# MSB-PCB-1R2.net
KiCad netlist of a schematic drawn in Altium Designer
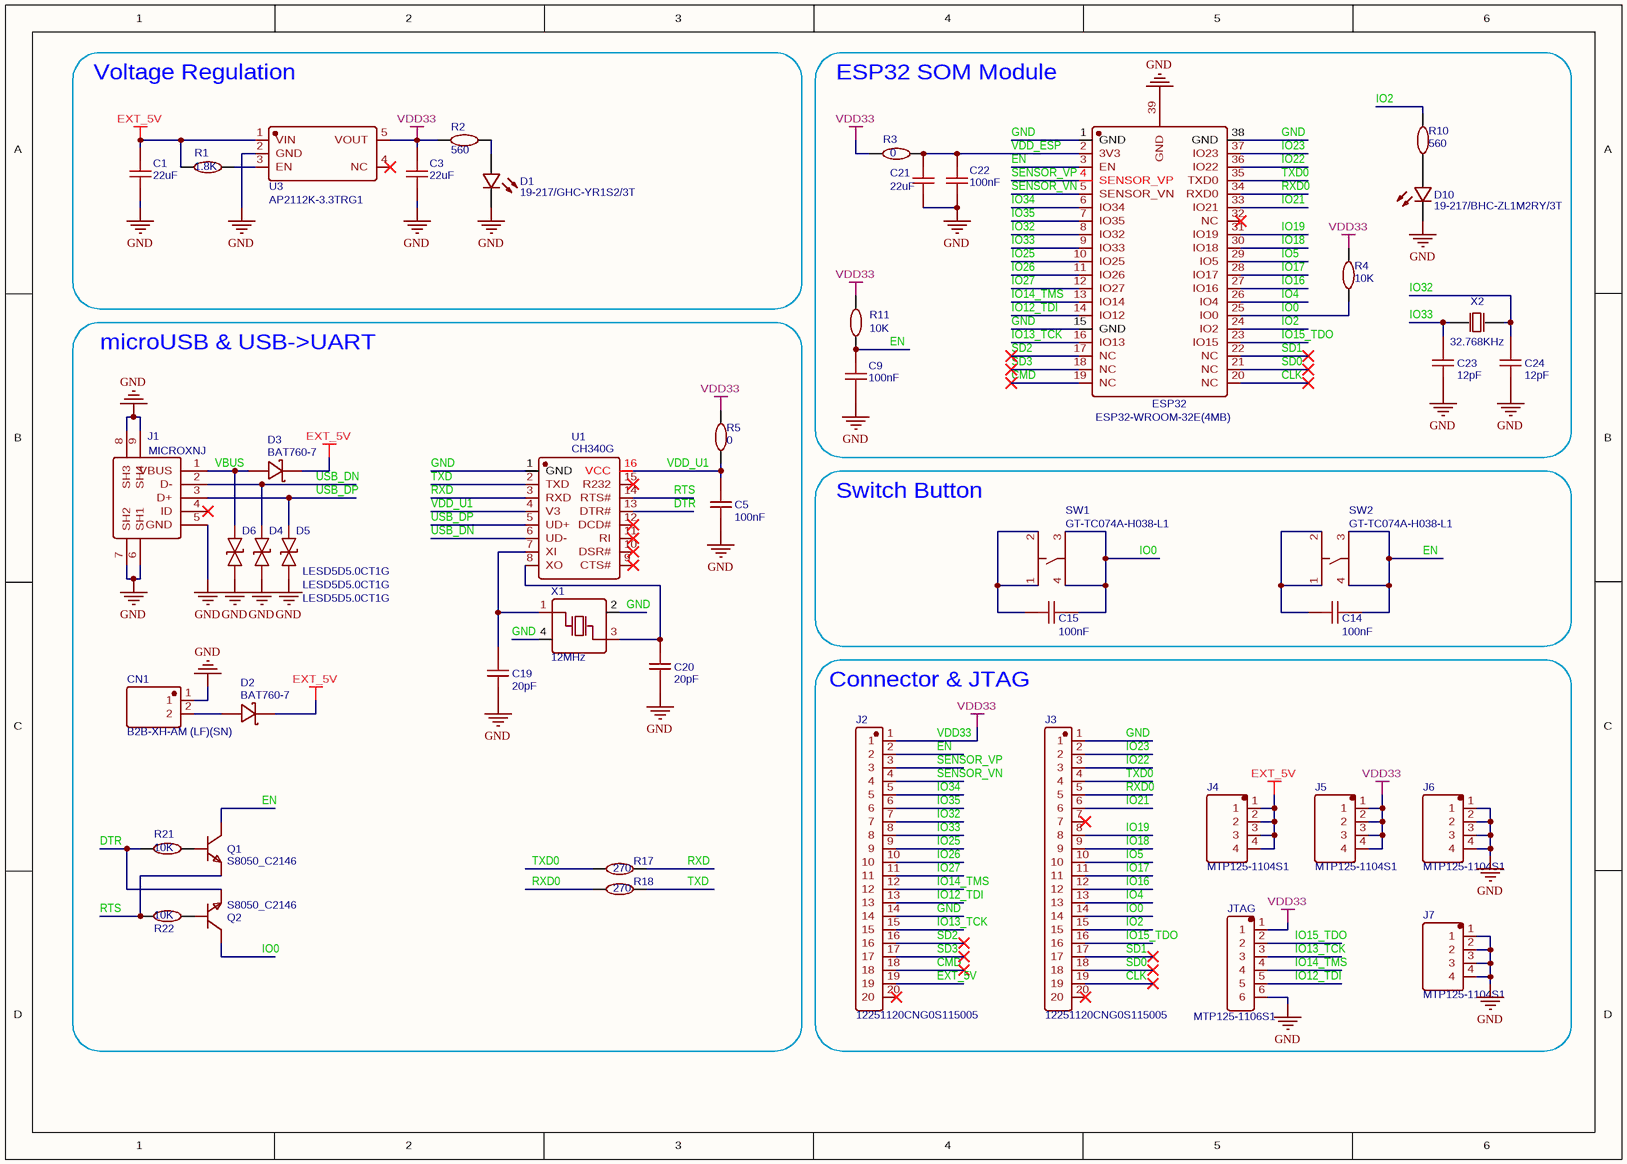
[diagram p0: MSB-PCB-1R2.schdoc]

(export (version "E")
  (design (tool "Eeschema 10.0.6"))
  (components
    (comp (ref "C1")
      (value "22uF")
      (footprint "C0603")
      (fields
        (field (name "BOM_SUPPLIER PART") "C167429")
        (field (name "BOM_MANUFACTURER PART") "GRM188R61A226ME15L")
        (field (name "CONTRIBUTOR") "LCSC")
      )
      (libsource (lib "altium-import") (part "root_1_22uF_"))
    )
    (comp (ref "C3")
      (value "22uF")
      (footprint "C0603")
      (fields
        (field (name "BOM_SUPPLIER PART") "C167429")
        (field (name "BOM_MANUFACTURER PART") "GRM188R61A226ME15L")
        (field (name "CONTRIBUTOR") "LCSC")
      )
      (libsource (lib "altium-import") (part "root_1_22uF_"))
    )
    (comp (ref "C5")
      (value "100nF")
      (footprint "C0603")
      (fields
        (field (name "BOM_MANUFACTURER PART") "CC0603KRX7R9BB104")
        (field (name "BOM_SUPPLIER PART") "C14663")
      )
      (libsource (lib "altium-import") (part "root_3_100nF_"))
    )
    (comp (ref "C9")
      (value "100nF")
      (footprint "C0603")
      (fields
        (field (name "BOM_MANUFACTURER PART") "CC0603KRX7R9BB104")
        (field (name "BOM_SUPPLIER PART") "C14663")
      )
      (libsource (lib "altium-import") (part "root_1_100nF_"))
    )
    (comp (ref "C14")
      (value "100nF")
      (footprint "C0603")
      (fields
        (field (name "BOM_MANUFACTURER PART") "CC0603KRX7R9BB104")
        (field (name "BOM_SUPPLIER PART") "C14663")
      )
      (libsource (lib "altium-import") (part "root_0_100nF_"))
    )
    (comp (ref "C15")
      (value "100nF")
      (footprint "C0603")
      (fields
        (field (name "BOM_MANUFACTURER PART") "CC0603KRX7R9BB104")
        (field (name "BOM_SUPPLIER PART") "C14663")
      )
      (libsource (lib "altium-import") (part "root_0_100nF_"))
    )
    (comp (ref "C19")
      (value "20pF")
      (footprint "C0603")
      (fields
        (field (name "BOM_SUPPLIER PART") "C376774")
        (field (name "BOM_MANUFACTURER PART") "TCC0603COG200J500CT")
        (field (name "CONTRIBUTOR") "LCSC")
      )
      (libsource (lib "altium-import") (part "root_0_20pF_"))
    )
    (comp (ref "C20")
      (value "20pF")
      (footprint "C0603")
      (fields
        (field (name "BOM_SUPPLIER PART") "C376774")
        (field (name "BOM_MANUFACTURER PART") "TCC0603COG200J500CT")
        (field (name "CONTRIBUTOR") "LCSC")
      )
      (libsource (lib "altium-import") (part "root_0_20pF_"))
    )
    (comp (ref "C21")
      (value "22uF")
      (footprint "C0603")
      (fields
        (field (name "BOM_SUPPLIER PART") "C167429")
        (field (name "BOM_MANUFACTURER PART") "GRM188R61A226ME15L")
        (field (name "CONTRIBUTOR") "LCSC")
      )
      (libsource (lib "altium-import") (part "root_1_22uF_"))
    )
    (comp (ref "C22")
      (value "100nF")
      (footprint "C0603")
      (fields
        (field (name "BOM_MANUFACTURER PART") "CC0603KRX7R9BB104")
        (field (name "BOM_SUPPLIER PART") "C14663")
      )
      (libsource (lib "altium-import") (part "root_1_100nF_"))
    )
    (comp (ref "C23")
      (value "12pF")
      (footprint "C0603")
      (fields
        (field (name "BOM_SUPPLIER PART") "C376767")
        (field (name "BOM_MANUFACTURER PART") "TCC0603COG120J500CT")
        (field (name "CONTRIBUTOR") "LCSC")
      )
      (libsource (lib "altium-import") (part "root_0_12pF_"))
    )
    (comp (ref "C24")
      (value "12pF")
      (footprint "C0603")
      (fields
        (field (name "BOM_SUPPLIER PART") "C376767")
        (field (name "BOM_MANUFACTURER PART") "TCC0603COG120J500CT")
        (field (name "CONTRIBUTOR") "LCSC")
      )
      (libsource (lib "altium-import") (part "root_0_12pF_"))
    )
    (comp (ref "CN1")
      (value "B2B-XH-AM (LF)(SN)")
      (footprint "CONN-TH_B2B-XH-AM-LF-SN")
      (fields (field (name "BOM_SUPPLIER PART") "C161869") (field (name "CONTRIBUTOR") "LCSC"))
      (libsource (lib "altium-import") (part "root_0_mirrored_B2B-XH-AM (LF)(SN)_"))
    )
    (comp (ref "D1")
      (value "19-217/GHC-YR1S2/3T")
      (footprint "LED0603-R-RD")
      (fields (field (name "BOM_SUPPLIER PART") "C72043"))
      (libsource (lib "altium-import") (part "root_3_19-217/GHC-YR1S2/3T_"))
    )
    (comp (ref "D2")
      (value "BAT760-7")
      (footprint "SOD-323_L1.8-W1.3-LS2.5-RD")
      (fields (field (name "BOM_SUPPLIER PART") "C124187") (field (name "CONTRIBUTOR") "LCSC"))
      (libsource (lib "altium-import") (part "root_2_BAT760-7_"))
    )
    (comp (ref "D3")
      (value "BAT760-7")
      (footprint "SOD-323_L1.8-W1.3-LS2.5-RD")
      (fields (field (name "BOM_SUPPLIER PART") "C124187") (field (name "CONTRIBUTOR") "LCSC"))
      (libsource (lib "altium-import") (part "root_2_BAT760-7_"))
    )
    (comp (ref "D4")
      (value "LESD5D5.0CT1G")
      (footprint "SOD-523_L1.2-W0.8-LS1.6-BI")
      (fields (field (name "BOM_SUPPLIER PART") "C383211") (field (name "CONTRIBUTOR") "LCSC"))
      (libsource (lib "altium-import") (part "root_1_LESD5D5.0CT1G_"))
    )
    (comp (ref "D5")
      (value "LESD5D5.0CT1G")
      (footprint "SOD-523_L1.2-W0.8-LS1.6-BI")
      (fields (field (name "BOM_SUPPLIER PART") "C383211") (field (name "CONTRIBUTOR") "LCSC"))
      (libsource (lib "altium-import") (part "root_1_LESD5D5.0CT1G_"))
    )
    (comp (ref "D6")
      (value "LESD5D5.0CT1G")
      (footprint "SOD-523_L1.2-W0.8-LS1.6-BI")
      (fields (field (name "BOM_SUPPLIER PART") "C383211") (field (name "CONTRIBUTOR") "LCSC"))
      (libsource (lib "altium-import") (part "root_1_LESD5D5.0CT1G_"))
    )
    (comp (ref "D10")
      (value "19-217/BHC-ZL1M2RY/3T")
      (footprint "LED0603-R-RD")
      (fields (field (name "BOM_SUPPLIER PART") "C72041"))
      (libsource (lib "altium-import") (part "root_1_19-217/BHC-ZL1M2RY/3T_"))
    )
    (comp (ref "ESP32")
      (value "ESP32-WROOM-32E(4MB)")
      (footprint "WIFI-SMD_ESP32-WROOM-32E")
      (fields (field (name "BOM_SUPPLIER PART") "C701341") (field (name "CONTRIBUTOR") "LCSC"))
      (libsource (lib "altium-import") (part "root_0_ESP32-WROOM-32E(4MB)_"))
    )
    (comp (ref "J1")
      (value "MICROXNJ")
      (footprint "MICRO-USB-SMD_MICROXNJ")
      (fields
        (field (name "BOM_SUPPLIER PART") "C404969")
        (field (name "BOM_MANUFACTURER PART") "MicroXNJ")
        (field (name "CONTRIBUTOR") "LCSC")
      )
      (libsource (lib "altium-import") (part "root_2_MICROXNJ_"))
    )
    (comp (ref "J2")
      (value "12251120CNG0S115005")
      (footprint "HDR-TH_19P-P2.54-V")
      (fields (field (name "BOM_SUPPLIER PART") "C429964") (field (name "CONTRIBUTOR") "LCSC"))
      (libsource (lib "altium-import") (part "root_0_mirrored_12251120CNG0S115005_"))
    )
    (comp (ref "J3")
      (value "12251120CNG0S115005")
      (footprint "HDR-TH_19P-P2.54-V")
      (fields (field (name "BOM_SUPPLIER PART") "C429964") (field (name "CONTRIBUTOR") "LCSC"))
      (libsource (lib "altium-import") (part "root_0_mirrored_12251120CNG0S115005_"))
    )
    (comp (ref "J4")
      (value "MTP125-1104S1")
      (footprint "HDR-TH_4P-P2.54-V")
      (fields (field (name "BOM_SUPPLIER PART") "C358686") (field (name "CONTRIBUTOR") "LCSC"))
      (libsource (lib "altium-import") (part "root_0_mirrored_MTP125-1104S1_"))
    )
    (comp (ref "J5")
      (value "MTP125-1104S1")
      (footprint "HDR-TH_4P-P2.54-V")
      (fields (field (name "BOM_SUPPLIER PART") "C358686") (field (name "CONTRIBUTOR") "LCSC"))
      (libsource (lib "altium-import") (part "root_0_mirrored_MTP125-1104S1_"))
    )
    (comp (ref "J6")
      (value "MTP125-1104S1")
      (footprint "HDR-TH_4P-P2.54-V")
      (fields (field (name "BOM_SUPPLIER PART") "C358686") (field (name "CONTRIBUTOR") "LCSC"))
      (libsource (lib "altium-import") (part "root_0_mirrored_MTP125-1104S1_"))
    )
    (comp (ref "J7")
      (value "MTP125-1104S1")
      (footprint "HDR-TH_4P-P2.54-V")
      (fields (field (name "BOM_SUPPLIER PART") "C358686") (field (name "CONTRIBUTOR") "LCSC"))
      (libsource (lib "altium-import") (part "root_0_mirrored_MTP125-1104S1_"))
    )
    (comp (ref "JTAG")
      (value "MTP125-1106S1")
      (footprint "HDR-TH_6P-P2.54-V")
      (fields (field (name "BOM_SUPPLIER PART") "C358688") (field (name "CONTRIBUTOR") "LCSC"))
      (libsource (lib "altium-import") (part "root_0_mirrored_MTP125-1106S1_"))
    )
    (comp (ref "Q1")
      (value "S8050_C2146")
      (footprint "SOT-23-3_L3.0-W1.7-P0.95-LS2.9-BR")
      (fields (field (name "BOM_MANUFACTURER PART") "S8050") (field (name "BOM_SUPPLIER PART") "C2146"))
      (libsource (lib "") (part "root_0_S8050_C2146__1"))
    )
    (comp (ref "Q2")
      (value "S8050_C2146")
      (footprint "SOT-23-3_L3.0-W1.7-P0.95-LS2.9-BR")
      (fields (field (name "BOM_MANUFACTURER PART") "S8050") (field (name "BOM_SUPPLIER PART") "C2146"))
      (libsource (lib "altium-import") (part "root_0_S8050_C2146_"))
    )
    (comp (ref "R1")
      (value "1.8K")
      (footprint "R0603")
      (fields
        (field (name "BOM_MANUFACTURER PART") "0603WAJ0182T5E")
        (field (name "BOM_SUPPLIER PART") "C25991")
      )
      (libsource (lib "altium-import") (part "root_0_1.8K_"))
    )
    (comp (ref "R2")
      (value "560")
      (footprint "R0603")
      (fields
        (field (name "BOM_MANUFACTURER PART") "0603WAF5600T5E")
        (field (name "BOM_SUPPLIER PART") "C23204")
      )
      (libsource (lib "altium-import") (part "root_2_560_"))
    )
    (comp (ref "R3")
      (value "0")
      (footprint "R0603")
      (fields
        (field (name "BOM_MANUFACTURER PART") "0603WAF0000T5E")
        (field (name "BOM_SUPPLIER PART") "C21189")
      )
      (libsource (lib "altium-import") (part "root_0_0_"))
    )
    (comp (ref "R4")
      (value "10K")
      (footprint "R0603")
      (fields
        (field (name "BOM_MANUFACTURER PART") "0603WAJ0103T5E")
        (field (name "BOM_SUPPLIER PART") "C15401")
      )
      (libsource (lib "altium-import") (part "root_1_10K_"))
    )
    (comp (ref "R5")
      (value "0")
      (footprint "R0603")
      (fields
        (field (name "BOM_MANUFACTURER PART") "0603WAF0000T5E")
        (field (name "BOM_SUPPLIER PART") "C21189")
      )
      (libsource (lib "altium-import") (part "root_1_0_"))
    )
    (comp (ref "R10")
      (value "560")
      (footprint "R0603")
      (fields
        (field (name "BOM_MANUFACTURER PART") "0603WAF5600T5E")
        (field (name "BOM_SUPPLIER PART") "C23204")
      )
      (libsource (lib "altium-import") (part "root_1_560_"))
    )
    (comp (ref "R11")
      (value "10K")
      (footprint "R0603")
      (fields
        (field (name "BOM_MANUFACTURER PART") "0603WAJ0103T5E")
        (field (name "BOM_SUPPLIER PART") "C15401")
      )
      (libsource (lib "altium-import") (part "root_1_10K_"))
    )
    (comp (ref "R17")
      (value "270")
      (footprint "R0603")
      (fields
        (field (name "BOM_MANUFACTURER PART") "0603WAJ0271T5E")
        (field (name "BOM_SUPPLIER PART") "C25223")
      )
      (libsource (lib "altium-import") (part "root_0_270_"))
    )
    (comp (ref "R18")
      (value "270")
      (footprint "R0603")
      (fields
        (field (name "BOM_MANUFACTURER PART") "0603WAJ0271T5E")
        (field (name "BOM_SUPPLIER PART") "C25223")
      )
      (libsource (lib "altium-import") (part "root_0_270_"))
    )
    (comp (ref "R21")
      (value "10K")
      (footprint "R0603")
      (fields
        (field (name "BOM_MANUFACTURER PART") "0603WAJ0103T5E")
        (field (name "BOM_SUPPLIER PART") "C15401")
      )
      (libsource (lib "altium-import") (part "root_0_10K_"))
    )
    (comp (ref "R22")
      (value "10K")
      (footprint "R0603")
      (fields
        (field (name "BOM_MANUFACTURER PART") "0603WAJ0103T5E")
        (field (name "BOM_SUPPLIER PART") "C15401")
      )
      (libsource (lib "altium-import") (part "root_0_10K_"))
    )
    (comp (ref "SW1")
      (value "GT-TC074A-H038-L1")
      (footprint "SW-SMD_4P-L4.5-W4.5-P3.00-LS7.0")
      (fields (field (name "BOM_SUPPLIER PART") "C843603") (field (name "CONTRIBUTOR") "LCSC"))
      (libsource (lib "altium-import") (part "root_1_GT-TC074A-H038-L1_"))
    )
    (comp (ref "SW2")
      (value "GT-TC074A-H038-L1")
      (footprint "SW-SMD_4P-L4.5-W4.5-P3.00-LS7.0")
      (fields (field (name "BOM_SUPPLIER PART") "C843603") (field (name "CONTRIBUTOR") "LCSC"))
      (libsource (lib "altium-import") (part "root_1_GT-TC074A-H038-L1_"))
    )
    (comp (ref "U1")
      (value "CH340G")
      (footprint "SOIC-16_L9.9-W3.9-P1.27-LS6.0-TL")
      (fields (field (name "BOM_SUPPLIER PART") "C14267"))
      (libsource (lib "altium-import") (part "root_0_CH340G_"))
    )
    (comp (ref "U3")
      (value "AP2112K-3.3TRG1")
      (footprint "SOT-25-5_L3.0-W1.8-P0.95-LS3.0-BR")
      (fields (field (name "BOM_SUPPLIER PART") "C51118") (field (name "CONTRIBUTOR") "LCSC"))
      (libsource (lib "altium-import") (part "root_0_AP2112K-3.3TRG1_"))
    )
    (comp (ref "X1")
      (value "12MHz")
      (footprint "OSC-SMD_4P-L3.2-W2.5-BL")
      (fields
        (field (name "BOM_MANUFACTURER PART") "X322512MSB4SI")
        (field (name "BOM_SUPPLIER PART") "C9002")
      )
      (libsource (lib "altium-import") (part "root_2_12MHz_"))
    )
    (comp (ref "X2")
      (value "32.768KHz")
      (footprint "OSC-SMD_L3.2-W1.5")
      (fields
        (field (name "BOM_SUPPLIER PART") "C271654")
        (field (name "BOM_MANUFACTURER PART") "SF32K32768D31T-12.5")
        (field (name "CONTRIBUTOR") "LCSC")
      )
      (libsource (lib "altium-import") (part "root_0_32.768KHz_"))
    )
  )
  (nets
    (net (code "1") (name "/CLK") (class "Default")
      (node (ref "ESP32") (pin "20") (pinfunction "NC_20") (pintype "passive"))
      (node (ref "J3") (pin "19") (pinfunction "19_19") (pintype "passive"))
    )
    (net (code "2") (name "/CMD") (class "Default")
      (node (ref "ESP32") (pin "19") (pinfunction "NC_19") (pintype "passive"))
      (node (ref "J2") (pin "18") (pinfunction "18_18") (pintype "passive"))
    )
    (net (code "3") (name "/DTR") (class "Default")
      (node (ref "Q2") (pin "2") (pinfunction "E_2") (pintype "passive"))
      (node (ref "R21") (pin "1") (pinfunction "1_1") (pintype "passive"))
      (node (ref "U1") (pin "13") (pinfunction "DTR#_13") (pintype "passive"))
    )
    (net (code "4") (name "/EN") (class "Default")
      (node (ref "C14") (pin "2") (pinfunction "2_2") (pintype "passive"))
      (node (ref "C9") (pin "2") (pinfunction "2_2") (pintype "passive"))
      (node (ref "ESP32") (pin "3") (pinfunction "EN_3") (pintype "passive"))
      (node (ref "J2") (pin "2") (pinfunction "2_2") (pintype "passive"))
      (node (ref "Q1") (pin "3") (pinfunction "C_3") (pintype "passive"))
      (node (ref "R11") (pin "1") (pinfunction "1_1") (pintype "passive"))
      (node (ref "SW2") (pin "3") (pinfunction "3_3") (pintype "passive"))
      (node (ref "SW2") (pin "4") (pinfunction "4_4") (pintype "passive"))
    )
    (net (code "5") (name "/IO0") (class "Default")
      (node (ref "C15") (pin "2") (pinfunction "2_2") (pintype "passive"))
      (node (ref "ESP32") (pin "25") (pinfunction "IO0_25") (pintype "passive"))
      (node (ref "J3") (pin "14") (pinfunction "14_14") (pintype "passive"))
      (node (ref "Q2") (pin "3") (pinfunction "C_3") (pintype "passive"))
      (node (ref "R4") (pin "1") (pinfunction "1_1") (pintype "passive"))
      (node (ref "SW1") (pin "3") (pinfunction "3_3") (pintype "passive"))
      (node (ref "SW1") (pin "4") (pinfunction "4_4") (pintype "passive"))
    )
    (net (code "6") (name "/IO2") (class "Default")
      (node (ref "ESP32") (pin "24") (pinfunction "IO2_24") (pintype "passive"))
      (node (ref "J3") (pin "15") (pinfunction "15_15") (pintype "passive"))
      (node (ref "R10") (pin "2") (pinfunction "2_2") (pintype "passive"))
    )
    (net (code "7") (name "/IO4") (class "Default")
      (node (ref "ESP32") (pin "26") (pinfunction "IO4_26") (pintype "passive"))
      (node (ref "J3") (pin "13") (pinfunction "13_13") (pintype "passive"))
    )
    (net (code "8") (name "/IO5") (class "Default")
      (node (ref "ESP32") (pin "29") (pinfunction "IO5_29") (pintype "passive"))
      (node (ref "J3") (pin "10") (pinfunction "10_10") (pintype "passive"))
    )
    (net (code "9") (name "/IO12_TDI") (class "Default")
      (node (ref "ESP32") (pin "14") (pinfunction "IO12_14") (pintype "passive"))
      (node (ref "J2") (pin "13") (pinfunction "13_13") (pintype "passive"))
      (node (ref "JTAG") (pin "5") (pinfunction "5_5") (pintype "passive"))
    )
    (net (code "10") (name "/IO13_TCK") (class "Default")
      (node (ref "ESP32") (pin "16") (pinfunction "IO13_16") (pintype "passive"))
      (node (ref "J2") (pin "15") (pinfunction "15_15") (pintype "passive"))
      (node (ref "JTAG") (pin "3") (pinfunction "3_3") (pintype "passive"))
    )
    (net (code "11") (name "/IO14_TMS") (class "Default")
      (node (ref "ESP32") (pin "13") (pinfunction "IO14_13") (pintype "passive"))
      (node (ref "J2") (pin "12") (pinfunction "12_12") (pintype "passive"))
      (node (ref "JTAG") (pin "4") (pinfunction "4_4") (pintype "passive"))
    )
    (net (code "12") (name "/IO15_TDO") (class "Default")
      (node (ref "ESP32") (pin "23") (pinfunction "IO15_23") (pintype "passive"))
      (node (ref "J3") (pin "16") (pinfunction "16_16") (pintype "passive"))
      (node (ref "JTAG") (pin "2") (pinfunction "2_2") (pintype "passive"))
    )
    (net (code "13") (name "/IO16") (class "Default")
      (node (ref "ESP32") (pin "27") (pinfunction "IO16_27") (pintype "passive"))
      (node (ref "J3") (pin "12") (pinfunction "12_12") (pintype "passive"))
    )
    (net (code "14") (name "/IO17") (class "Default")
      (node (ref "ESP32") (pin "28") (pinfunction "IO17_28") (pintype "passive"))
      (node (ref "J3") (pin "11") (pinfunction "11_11") (pintype "passive"))
    )
    (net (code "15") (name "/IO18") (class "Default")
      (node (ref "ESP32") (pin "30") (pinfunction "IO18_30") (pintype "passive"))
      (node (ref "J3") (pin "9") (pinfunction "9_9") (pintype "passive"))
    )
    (net (code "16") (name "/IO19") (class "Default")
      (node (ref "ESP32") (pin "31") (pinfunction "IO19_31") (pintype "passive"))
      (node (ref "J3") (pin "8") (pinfunction "8_8") (pintype "passive"))
    )
    (net (code "17") (name "/IO21") (class "Default")
      (node (ref "ESP32") (pin "33") (pinfunction "IO21_33") (pintype "passive"))
      (node (ref "J3") (pin "6") (pinfunction "6_6") (pintype "passive"))
    )
    (net (code "18") (name "/IO22") (class "Default")
      (node (ref "ESP32") (pin "36") (pinfunction "IO22_36") (pintype "passive"))
      (node (ref "J3") (pin "3") (pinfunction "3_3") (pintype "passive"))
    )
    (net (code "19") (name "/IO23") (class "Default")
      (node (ref "ESP32") (pin "37") (pinfunction "IO23_37") (pintype "passive"))
      (node (ref "J3") (pin "2") (pinfunction "2_2") (pintype "passive"))
    )
    (net (code "20") (name "/IO25") (class "Default")
      (node (ref "ESP32") (pin "10") (pinfunction "IO25_10") (pintype "passive"))
      (node (ref "J2") (pin "9") (pinfunction "9_9") (pintype "passive"))
    )
    (net (code "21") (name "/IO26") (class "Default")
      (node (ref "ESP32") (pin "11") (pinfunction "IO26_11") (pintype "passive"))
      (node (ref "J2") (pin "10") (pinfunction "10_10") (pintype "passive"))
    )
    (net (code "22") (name "/IO27") (class "Default")
      (node (ref "ESP32") (pin "12") (pinfunction "IO27_12") (pintype "passive"))
      (node (ref "J2") (pin "11") (pinfunction "11_11") (pintype "passive"))
    )
    (net (code "23") (name "/IO32") (class "Default")
      (node (ref "C24") (pin "2") (pinfunction "2_2") (pintype "passive"))
      (node (ref "ESP32") (pin "8") (pinfunction "IO32_8") (pintype "passive"))
      (node (ref "J2") (pin "7") (pinfunction "7_7") (pintype "passive"))
      (node (ref "X2") (pin "2") (pinfunction "OSC2_2") (pintype "passive"))
    )
    (net (code "24") (name "/IO33") (class "Default")
      (node (ref "C23") (pin "2") (pinfunction "2_2") (pintype "passive"))
      (node (ref "ESP32") (pin "9") (pinfunction "IO33_9") (pintype "passive"))
      (node (ref "J2") (pin "8") (pinfunction "8_8") (pintype "passive"))
      (node (ref "X2") (pin "1") (pinfunction "OSC1_1") (pintype "passive"))
    )
    (net (code "25") (name "/IO34") (class "Default")
      (node (ref "ESP32") (pin "6") (pinfunction "IO34_6") (pintype "passive"))
      (node (ref "J2") (pin "5") (pinfunction "5_5") (pintype "passive"))
    )
    (net (code "26") (name "/IO35") (class "Default")
      (node (ref "ESP32") (pin "7") (pinfunction "IO35_7") (pintype "passive"))
      (node (ref "J2") (pin "6") (pinfunction "6_6") (pintype "passive"))
    )
    (net (code "27") (name "/RTS") (class "Default")
      (node (ref "Q1") (pin "2") (pinfunction "E_2") (pintype "passive"))
      (node (ref "R22") (pin "1") (pinfunction "1_1") (pintype "passive"))
      (node (ref "U1") (pin "14") (pinfunction "RTS#_14") (pintype "passive"))
    )
    (net (code "28") (name "/RXD") (class "Default")
      (node (ref "R17") (pin "2") (pinfunction "2_2") (pintype "passive"))
      (node (ref "U1") (pin "3") (pinfunction "RXD_3") (pintype "passive"))
    )
    (net (code "29") (name "/RXD0") (class "Default")
      (node (ref "ESP32") (pin "34") (pinfunction "RXD0_34") (pintype "passive"))
      (node (ref "J3") (pin "5") (pinfunction "5_5") (pintype "passive"))
      (node (ref "R18") (pin "1") (pinfunction "1_1") (pintype "passive"))
    )
    (net (code "30") (name "/SD0") (class "Default")
      (node (ref "ESP32") (pin "21") (pinfunction "NC_21") (pintype "passive"))
      (node (ref "J3") (pin "18") (pinfunction "18_18") (pintype "passive"))
    )
    (net (code "31") (name "/SD1") (class "Default")
      (node (ref "ESP32") (pin "22") (pinfunction "NC_22") (pintype "passive"))
      (node (ref "J3") (pin "17") (pinfunction "17_17") (pintype "passive"))
    )
    (net (code "32") (name "/SD2") (class "Default")
      (node (ref "ESP32") (pin "17") (pinfunction "NC_17") (pintype "passive"))
      (node (ref "J2") (pin "16") (pinfunction "16_16") (pintype "passive"))
    )
    (net (code "33") (name "/SD3") (class "Default")
      (node (ref "ESP32") (pin "18") (pinfunction "NC_18") (pintype "passive"))
      (node (ref "J2") (pin "17") (pinfunction "17_17") (pintype "passive"))
    )
    (net (code "34") (name "/SENSOR_VN") (class "Default")
      (node (ref "ESP32") (pin "5") (pinfunction "SENSOR_VN_5") (pintype "passive"))
      (node (ref "J2") (pin "4") (pinfunction "4_4") (pintype "passive"))
    )
    (net (code "35") (name "/SENSOR_VP") (class "Default")
      (node (ref "ESP32") (pin "4") (pinfunction "SENSOR_VP_4") (pintype "passive"))
      (node (ref "J2") (pin "3") (pinfunction "3_3") (pintype "passive"))
    )
    (net (code "36") (name "/TXD") (class "Default")
      (node (ref "R18") (pin "2") (pinfunction "2_2") (pintype "passive"))
      (node (ref "U1") (pin "2") (pinfunction "TXD_2") (pintype "passive"))
    )
    (net (code "37") (name "/TXD0") (class "Default")
      (node (ref "ESP32") (pin "35") (pinfunction "TXD0_35") (pintype "passive"))
      (node (ref "J3") (pin "4") (pinfunction "4_4") (pintype "passive"))
      (node (ref "R17") (pin "1") (pinfunction "1_1") (pintype "passive"))
    )
    (net (code "38") (name "/USB_DN") (class "Default")
      (node (ref "D4") (pin "2") (pinfunction "2_2") (pintype "passive"))
      (node (ref "J1") (pin "2") (pinfunction "D-_2") (pintype "passive"))
      (node (ref "U1") (pin "6") (pinfunction "UD-_6") (pintype "passive"))
    )
    (net (code "39") (name "/USB_DP") (class "Default")
      (node (ref "D5") (pin "2") (pinfunction "2_2") (pintype "passive"))
      (node (ref "J1") (pin "3") (pinfunction "D+_3") (pintype "passive"))
      (node (ref "U1") (pin "5") (pinfunction "UD+_5") (pintype "passive"))
    )
    (net (code "40") (name "/VBUS") (class "Default")
      (node (ref "D3") (pin "2") (pinfunction "2_2") (pintype "passive"))
      (node (ref "D6") (pin "2") (pinfunction "2_2") (pintype "passive"))
      (node (ref "J1") (pin "1") (pinfunction "VBUS_1") (pintype "passive"))
    )
    (net (code "41") (name "/VDD_ESP") (class "Default")
      (node (ref "C21") (pin "2") (pinfunction "2_2") (pintype "passive"))
      (node (ref "C22") (pin "2") (pinfunction "2_2") (pintype "passive"))
      (node (ref "ESP32") (pin "2") (pinfunction "3V3_2") (pintype "passive"))
      (node (ref "R3") (pin "2") (pinfunction "2_2") (pintype "passive"))
    )
    (net (code "42") (name "/VDD_U1") (class "Default")
      (node (ref "C5") (pin "1") (pinfunction "1_1") (pintype "passive"))
      (node (ref "R5") (pin "1") (pinfunction "1_1") (pintype "passive"))
      (node (ref "U1") (pin "16") (pinfunction "VCC_16") (pintype "passive"))
      (node (ref "U1") (pin "4") (pinfunction "V3_4") (pintype "passive"))
    )
    (net (code "43") (name "EXT_5V") (class "Default")
      (node (ref "C1") (pin "2") (pinfunction "2_2") (pintype "passive"))
      (node (ref "D2") (pin "1") (pinfunction "1_1") (pintype "passive"))
      (node (ref "D3") (pin "1") (pinfunction "1_1") (pintype "passive"))
      (node (ref "J2") (pin "19") (pinfunction "19_19") (pintype "passive"))
      (node (ref "J4") (pin "1") (pinfunction "1_1") (pintype "passive"))
      (node (ref "J4") (pin "2") (pinfunction "2_2") (pintype "passive"))
      (node (ref "J4") (pin "3") (pinfunction "3_3") (pintype "passive"))
      (node (ref "J4") (pin "4") (pinfunction "4_4") (pintype "passive"))
      (node (ref "R1") (pin "1") (pinfunction "1_1") (pintype "passive"))
      (node (ref "U3") (pin "1") (pinfunction "VIN_1") (pintype "passive"))
    )
    (net (code "44") (name "GND") (class "Default")
      (node (ref "C1") (pin "1") (pinfunction "1_1") (pintype "passive"))
      (node (ref "C19") (pin "1") (pinfunction "1_1") (pintype "passive"))
      (node (ref "C20") (pin "1") (pinfunction "1_1") (pintype "passive"))
      (node (ref "C21") (pin "1") (pinfunction "1_1") (pintype "passive"))
      (node (ref "C22") (pin "1") (pinfunction "1_1") (pintype "passive"))
      (node (ref "C23") (pin "1") (pinfunction "1_1") (pintype "passive"))
      (node (ref "C24") (pin "1") (pinfunction "1_1") (pintype "passive"))
      (node (ref "C3") (pin "1") (pinfunction "1_1") (pintype "passive"))
      (node (ref "C5") (pin "2") (pinfunction "2_2") (pintype "passive"))
      (node (ref "C9") (pin "1") (pinfunction "1_1") (pintype "passive"))
      (node (ref "CN1") (pin "1") (pinfunction "1_1") (pintype "passive"))
      (node (ref "D1") (pin "2") (pinfunction "C_2") (pintype "passive"))
      (node (ref "D10") (pin "2") (pinfunction "C_2") (pintype "passive"))
      (node (ref "D4") (pin "1") (pinfunction "1_1") (pintype "passive"))
      (node (ref "D5") (pin "1") (pinfunction "1_1") (pintype "passive"))
      (node (ref "D6") (pin "1") (pinfunction "1_1") (pintype "passive"))
      (node (ref "ESP32") (pin "1") (pinfunction "GND_1") (pintype "passive"))
      (node (ref "ESP32") (pin "15") (pinfunction "GND_15") (pintype "passive"))
      (node (ref "ESP32") (pin "38") (pinfunction "GND_38") (pintype "passive"))
      (node (ref "ESP32") (pin "39") (pinfunction "GND_39") (pintype "passive"))
      (node (ref "J1") (pin "5") (pinfunction "GND_5") (pintype "passive"))
      (node (ref "J1") (pin "6") (pinfunction "SH1_6") (pintype "passive"))
      (node (ref "J1") (pin "7") (pinfunction "SH2_7") (pintype "passive"))
      (node (ref "J1") (pin "8") (pinfunction "SH3_8") (pintype "passive"))
      (node (ref "J1") (pin "9") (pinfunction "SH4_9") (pintype "passive"))
      (node (ref "J2") (pin "14") (pinfunction "14_14") (pintype "passive"))
      (node (ref "J3") (pin "1") (pinfunction "1_1") (pintype "passive"))
      (node (ref "J6") (pin "1") (pinfunction "1_1") (pintype "passive"))
      (node (ref "J6") (pin "2") (pinfunction "2_2") (pintype "passive"))
      (node (ref "J6") (pin "3") (pinfunction "3_3") (pintype "passive"))
      (node (ref "J6") (pin "4") (pinfunction "4_4") (pintype "passive"))
      (node (ref "J7") (pin "1") (pinfunction "1_1") (pintype "passive"))
      (node (ref "J7") (pin "2") (pinfunction "2_2") (pintype "passive"))
      (node (ref "J7") (pin "3") (pinfunction "3_3") (pintype "passive"))
      (node (ref "J7") (pin "4") (pinfunction "4_4") (pintype "passive"))
      (node (ref "JTAG") (pin "6") (pinfunction "6_6") (pintype "passive"))
      (node (ref "U1") (pin "1") (pinfunction "GND_1") (pintype "passive"))
      (node (ref "U3") (pin "2") (pinfunction "GND_2") (pintype "passive"))
      (node (ref "X1") (pin "2") (pinfunction "GND_2") (pintype "passive"))
      (node (ref "X1") (pin "4") (pinfunction "GND_4") (pintype "passive"))
    )
    (net (code "45") (name "Net-(C14-Pad1)") (class "Default")
      (node (ref "C14") (pin "1") (pinfunction "1_1") (pintype "passive"))
      (node (ref "SW2") (pin "1") (pinfunction "1_1") (pintype "passive"))
      (node (ref "SW2") (pin "2") (pinfunction "2_2") (pintype "passive"))
    )
    (net (code "46") (name "Net-(C15-Pad1)") (class "Default")
      (node (ref "C15") (pin "1") (pinfunction "1_1") (pintype "passive"))
      (node (ref "SW1") (pin "1") (pinfunction "1_1") (pintype "passive"))
      (node (ref "SW1") (pin "2") (pinfunction "2_2") (pintype "passive"))
    )
    (net (code "47") (name "Net-(CN1-Pad2)") (class "Default")
      (node (ref "CN1") (pin "2") (pinfunction "2_2") (pintype "passive"))
      (node (ref "D2") (pin "2") (pinfunction "2_2") (pintype "passive"))
    )
    (net (code "48") (name "Net-(D1-A)") (class "Default")
      (node (ref "D1") (pin "1") (pinfunction "A_1") (pintype "passive"))
      (node (ref "R2") (pin "1") (pinfunction "1_1") (pintype "passive"))
    )
    (net (code "49") (name "Net-(D10-A)") (class "Default")
      (node (ref "D10") (pin "1") (pinfunction "A_1") (pintype "passive"))
      (node (ref "R10") (pin "1") (pinfunction "1_1") (pintype "passive"))
    )
    (net (code "50") (name "Net-(Q1-B)") (class "Default")
      (node (ref "Q1") (pin "1") (pinfunction "B_1") (pintype "passive"))
      (node (ref "R21") (pin "2") (pinfunction "2_2") (pintype "passive"))
    )
    (net (code "51") (name "Net-(Q2-B)") (class "Default")
      (node (ref "Q2") (pin "1") (pinfunction "B_1") (pintype "passive"))
      (node (ref "R22") (pin "2") (pinfunction "2_2") (pintype "passive"))
    )
    (net (code "52") (name "Net-(U1-XI)") (class "Default")
      (node (ref "C19") (pin "2") (pinfunction "2_2") (pintype "passive"))
      (node (ref "U1") (pin "7") (pinfunction "XI_7") (pintype "passive"))
      (node (ref "X1") (pin "1") (pinfunction "OSC1_1") (pintype "passive"))
    )
    (net (code "53") (name "Net-(U1-XO)") (class "Default")
      (node (ref "C20") (pin "2") (pinfunction "2_2") (pintype "passive"))
      (node (ref "U1") (pin "8") (pinfunction "XO_8") (pintype "passive"))
      (node (ref "X1") (pin "3") (pinfunction "OSC2_3") (pintype "passive"))
    )
    (net (code "54") (name "Net-(U3-EN)") (class "Default")
      (node (ref "R1") (pin "2") (pinfunction "2_2") (pintype "passive"))
      (node (ref "U3") (pin "3") (pinfunction "EN_3") (pintype "passive"))
    )
    (net (code "55") (name "VDD33") (class "Default")
      (node (ref "C3") (pin "2") (pinfunction "2_2") (pintype "passive"))
      (node (ref "J2") (pin "1") (pinfunction "1_1") (pintype "passive"))
      (node (ref "J5") (pin "1") (pinfunction "1_1") (pintype "passive"))
      (node (ref "J5") (pin "2") (pinfunction "2_2") (pintype "passive"))
      (node (ref "J5") (pin "3") (pinfunction "3_3") (pintype "passive"))
      (node (ref "J5") (pin "4") (pinfunction "4_4") (pintype "passive"))
      (node (ref "JTAG") (pin "1") (pinfunction "1_1") (pintype "passive"))
      (node (ref "R11") (pin "2") (pinfunction "2_2") (pintype "passive"))
      (node (ref "R2") (pin "2") (pinfunction "2_2") (pintype "passive"))
      (node (ref "R3") (pin "1") (pinfunction "1_1") (pintype "passive"))
      (node (ref "R4") (pin "2") (pinfunction "2_2") (pintype "passive"))
      (node (ref "R5") (pin "2") (pinfunction "2_2") (pintype "passive"))
      (node (ref "U3") (pin "5") (pinfunction "VOUT_5") (pintype "passive"))
    )
    (net (code "56") (name "unconnected-(ESP32-NC-Pad32)") (class "Default")
      (node (ref "ESP32") (pin "32") (pinfunction "NC_32") (pintype "passive+no_connect"))
    )
    (net (code "57") (name "unconnected-(J1-ID-Pad4)") (class "Default")
      (node (ref "J1") (pin "4") (pinfunction "ID_4") (pintype "passive+no_connect"))
    )
    (net (code "58") (name "unconnected-(J2-Pad20)") (class "Default")
      (node (ref "J2") (pin "20") (pinfunction "20_20") (pintype "passive+no_connect"))
    )
    (net (code "59") (name "unconnected-(J3-Pad7)") (class "Default")
      (node (ref "J3") (pin "7") (pinfunction "7_7") (pintype "passive+no_connect"))
    )
    (net (code "60") (name "unconnected-(J3-Pad20)") (class "Default")
      (node (ref "J3") (pin "20") (pinfunction "20_20") (pintype "passive+no_connect"))
    )
    (net (code "61") (name "unconnected-(U1-CTS#-Pad9)") (class "Default")
      (node (ref "U1") (pin "9") (pinfunction "CTS#_9") (pintype "passive+no_connect"))
    )
    (net (code "62") (name "unconnected-(U1-DCD#-Pad12)") (class "Default")
      (node (ref "U1") (pin "12") (pinfunction "DCD#_12") (pintype "passive+no_connect"))
    )
    (net (code "63") (name "unconnected-(U1-DSR#-Pad10)") (class "Default")
      (node (ref "U1") (pin "10") (pinfunction "DSR#_10") (pintype "passive+no_connect"))
    )
    (net (code "64") (name "unconnected-(U1-R232-Pad15)") (class "Default")
      (node (ref "U1") (pin "15") (pinfunction "R232_15") (pintype "passive+no_connect"))
    )
    (net (code "65") (name "unconnected-(U1-RI-Pad11)") (class "Default")
      (node (ref "U1") (pin "11") (pinfunction "RI_11") (pintype "passive+no_connect"))
    )
    (net (code "66") (name "unconnected-(U3-NC-Pad4)") (class "Default")
      (node (ref "U3") (pin "4") (pinfunction "NC_4") (pintype "passive+no_connect"))
    )
  )
)
